# Main_Board_-v1_1.net
KiCad netlist of a schematic drawn in EAGLE
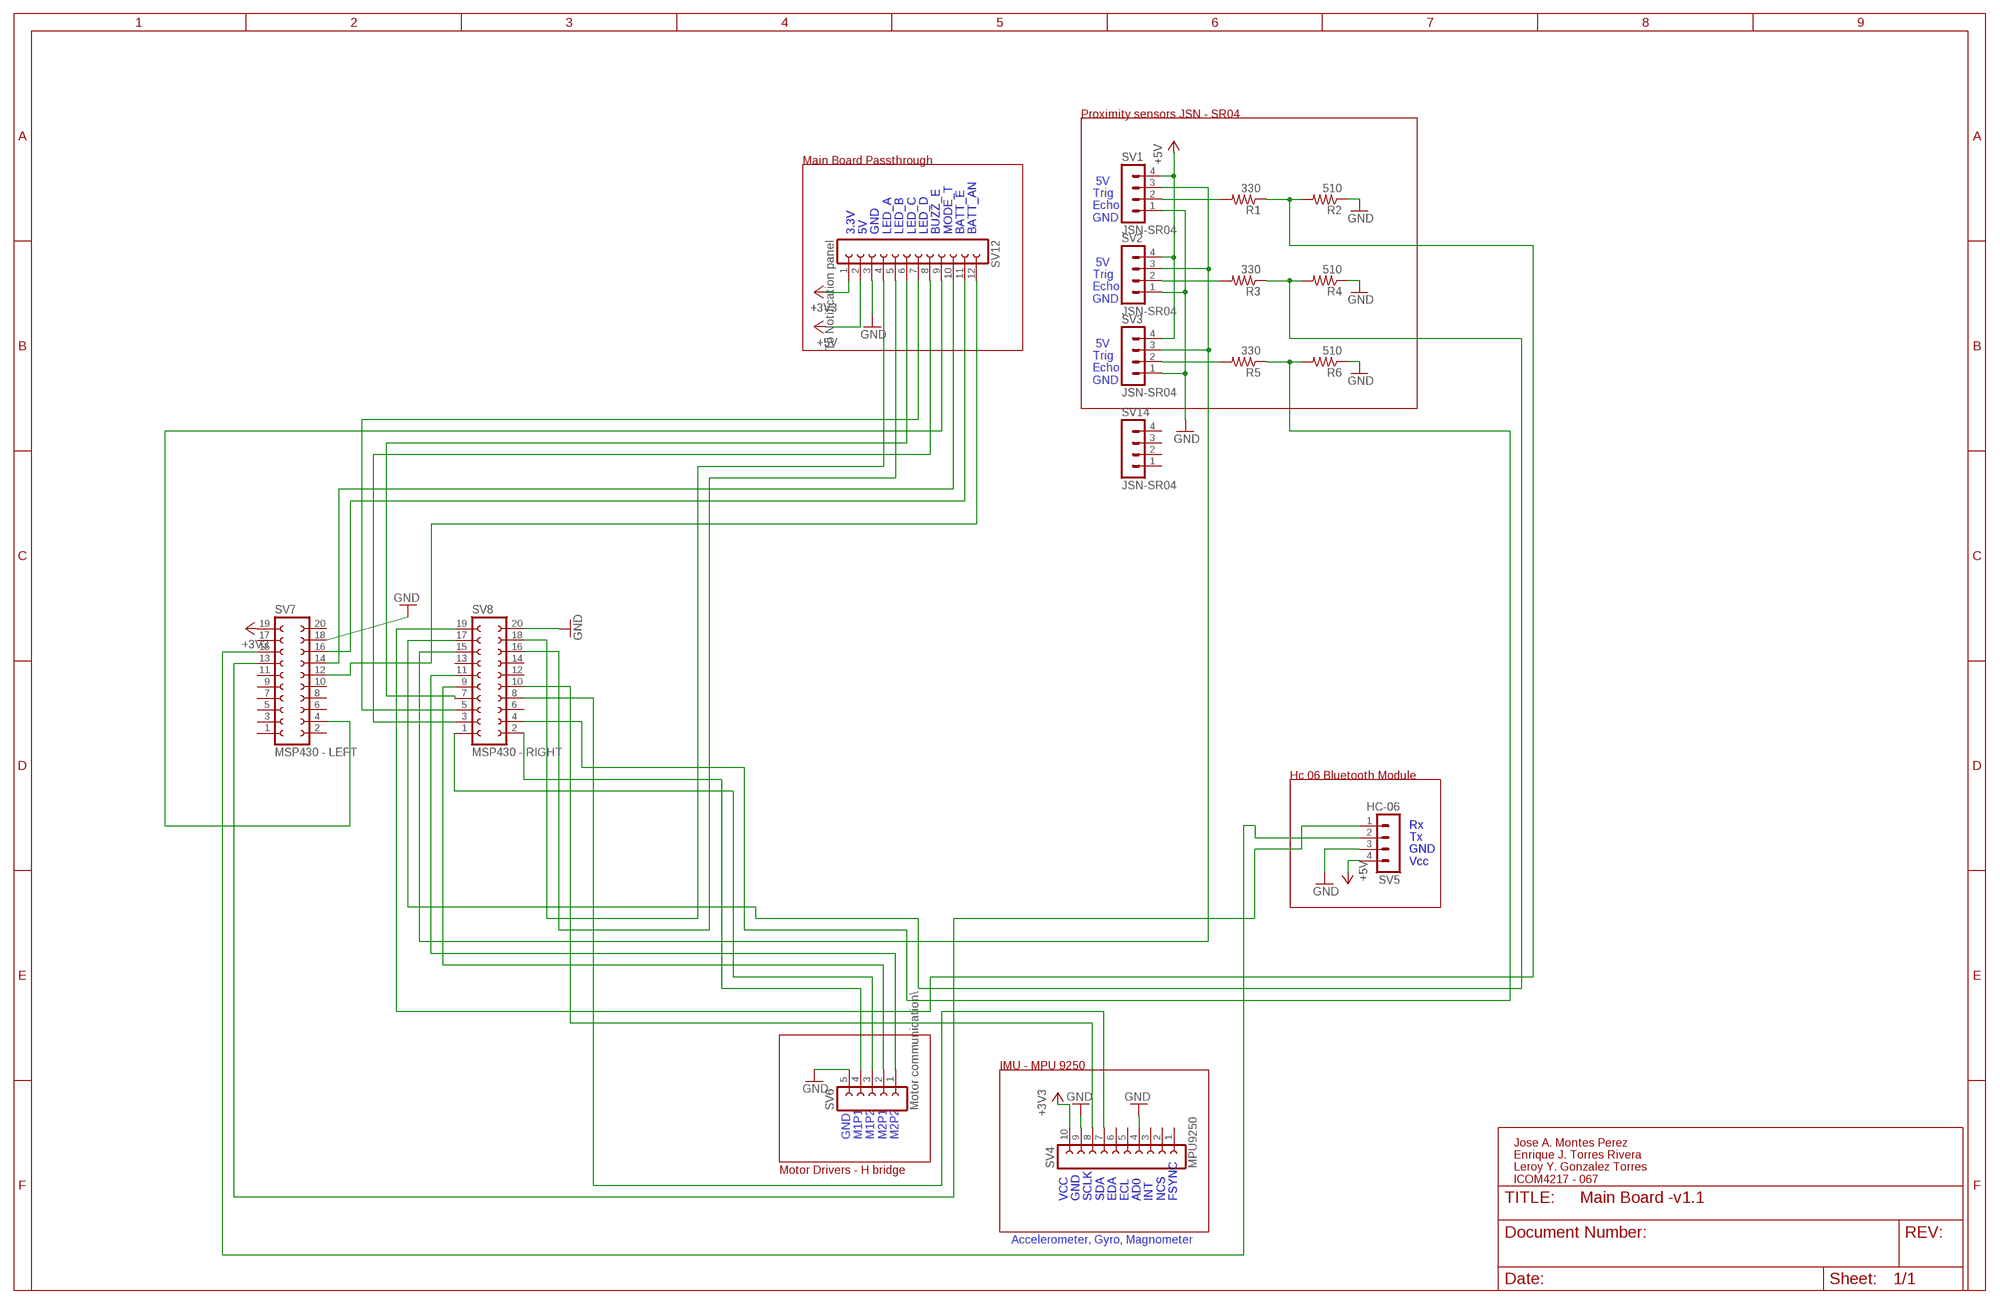
[diagram p0: schematic, sheet 1]

(export (version "E")
  (design (tool "Eeschema 10.0.6"))
  (components
    (comp (ref "R1")
      (value "330")
      (footprint "eagle-import:0207_10")
      (libsource (lib "eagle-import") (part "R-US_0207/10"))
    )
    (comp (ref "R2")
      (value "510")
      (footprint "eagle-import:0207_10")
      (libsource (lib "eagle-import") (part "R-US_0207/10"))
    )
    (comp (ref "R3")
      (value "330")
      (footprint "eagle-import:0207_10")
      (libsource (lib "eagle-import") (part "R-US_0207/10"))
    )
    (comp (ref "R4")
      (value "510")
      (footprint "eagle-import:0207_10")
      (libsource (lib "eagle-import") (part "R-US_0207/10"))
    )
    (comp (ref "R5")
      (value "330")
      (footprint "eagle-import:0207_10")
      (libsource (lib "eagle-import") (part "R-US_0207/10"))
    )
    (comp (ref "R6")
      (value "510")
      (footprint "eagle-import:0207_10")
      (libsource (lib "eagle-import") (part "R-US_0207/10"))
    )
    (comp (ref "SV1")
      (value "JSN-SR04")
      (footprint "eagle-import:MA04-1")
      (libsource (lib "eagle-import") (part "MA04-1"))
    )
    (comp (ref "SV2")
      (value "JSN-SR04")
      (footprint "eagle-import:MA04-1")
      (libsource (lib "eagle-import") (part "MA04-1"))
    )
    (comp (ref "SV3")
      (value "JSN-SR04")
      (footprint "eagle-import:MA04-1")
      (libsource (lib "eagle-import") (part "MA04-1"))
    )
    (comp (ref "SV4")
      (value "MPU9250")
      (footprint "eagle-import:FE10")
      (libsource (lib "eagle-import") (part "FE10-1"))
    )
    (comp (ref "SV5")
      (value "HC-06")
      (footprint "eagle-import:MA04-1")
      (libsource (lib "eagle-import") (part "MA04-1"))
    )
    (comp (ref "SV6")
      (value "Motor communication\\")
      (footprint "eagle-import:FE05-1")
      (libsource (lib "eagle-import") (part "FE05-1"))
    )
    (comp (ref "SV7")
      (value "MSP430 - LEFT")
      (footprint "eagle-import:FE10-2")
      (libsource (lib "eagle-import") (part "FE10-2"))
    )
    (comp (ref "SV8")
      (value "MSP430 - RIGHT")
      (footprint "eagle-import:FE10-2")
      (libsource (lib "eagle-import") (part "FE10-2"))
    )
    (comp (ref "SV12")
      (value "To Notification panel")
      (footprint "eagle-import:FE12")
      (libsource (lib "eagle-import") (part "FE12-1"))
    )
    (comp (ref "SV14")
      (value "JSN-SR04")
      (footprint "eagle-import:MA04-1")
      (libsource (lib "eagle-import") (part "MA04-1"))
    )
  )
  (nets
    (net (code "1") (name "+3V3") (class "Default")
      (node (ref "SV12") (pin "1") (pinfunction "1_1") (pintype "passive"))
      (node (ref "SV4") (pin "10") (pinfunction "10_10") (pintype "passive"))
      (node (ref "SV7") (pin "19") (pinfunction "19_19") (pintype "passive"))
    )
    (net (code "2") (name "+5V") (class "Default")
      (node (ref "SV1") (pin "4") (pinfunction "4_4") (pintype "passive"))
      (node (ref "SV12") (pin "2") (pinfunction "2_2") (pintype "passive"))
      (node (ref "SV2") (pin "4") (pinfunction "4_4") (pintype "passive"))
      (node (ref "SV3") (pin "4") (pinfunction "4_4") (pintype "passive"))
      (node (ref "SV5") (pin "4") (pinfunction "4_4") (pintype "passive"))
    )
    (net (code "3") (name "GND") (class "Default")
      (node (ref "R2") (pin "1") (pinfunction "1_1") (pintype "passive"))
      (node (ref "R4") (pin "1") (pinfunction "1_1") (pintype "passive"))
      (node (ref "R6") (pin "1") (pinfunction "1_1") (pintype "passive"))
      (node (ref "SV1") (pin "1") (pinfunction "1_1") (pintype "passive"))
      (node (ref "SV12") (pin "3") (pinfunction "3_3") (pintype "passive"))
      (node (ref "SV2") (pin "1") (pinfunction "1_1") (pintype "passive"))
      (node (ref "SV3") (pin "1") (pinfunction "1_1") (pintype "passive"))
      (node (ref "SV4") (pin "4") (pinfunction "4_4") (pintype "passive"))
      (node (ref "SV4") (pin "9") (pinfunction "9_9") (pintype "passive"))
      (node (ref "SV5") (pin "3") (pinfunction "3_3") (pintype "passive"))
      (node (ref "SV6") (pin "5") (pinfunction "5_5") (pintype "passive"))
      (node (ref "SV7") (pin "18") (pinfunction "18_18") (pintype "passive"))
      (node (ref "SV8") (pin "20") (pinfunction "20_20") (pintype "passive"))
    )
    (net (code "4") (name "Net-(R1-Pad1)") (class "Default")
      (node (ref "R1") (pin "1") (pinfunction "1_1") (pintype "passive"))
      (node (ref "R2") (pin "2") (pinfunction "2_2") (pintype "passive"))
      (node (ref "SV8") (pin "19") (pinfunction "19_19") (pintype "passive"))
    )
    (net (code "5") (name "Net-(R1-Pad2)") (class "Default")
      (node (ref "R1") (pin "2") (pinfunction "2_2") (pintype "passive"))
      (node (ref "SV1") (pin "2") (pinfunction "2_2") (pintype "passive"))
    )
    (net (code "6") (name "Net-(R3-Pad1)") (class "Default")
      (node (ref "R3") (pin "1") (pinfunction "1_1") (pintype "passive"))
      (node (ref "R4") (pin "2") (pinfunction "2_2") (pintype "passive"))
      (node (ref "SV8") (pin "17") (pinfunction "17_17") (pintype "passive"))
    )
    (net (code "7") (name "Net-(R3-Pad2)") (class "Default")
      (node (ref "R3") (pin "2") (pinfunction "2_2") (pintype "passive"))
      (node (ref "SV2") (pin "2") (pinfunction "2_2") (pintype "passive"))
    )
    (net (code "8") (name "Net-(R5-Pad1)") (class "Default")
      (node (ref "R5") (pin "1") (pinfunction "1_1") (pintype "passive"))
      (node (ref "R6") (pin "2") (pinfunction "2_2") (pintype "passive"))
      (node (ref "SV8") (pin "4") (pinfunction "4_4") (pintype "passive"))
    )
    (net (code "9") (name "Net-(R5-Pad2)") (class "Default")
      (node (ref "R5") (pin "2") (pinfunction "2_2") (pintype "passive"))
      (node (ref "SV3") (pin "2") (pinfunction "2_2") (pintype "passive"))
    )
    (net (code "10") (name "Net-(SV1-Pad3)") (class "Default")
      (node (ref "SV1") (pin "3") (pinfunction "3_3") (pintype "passive"))
      (node (ref "SV2") (pin "3") (pinfunction "3_3") (pintype "passive"))
      (node (ref "SV3") (pin "3") (pinfunction "3_3") (pintype "passive"))
      (node (ref "SV8") (pin "15") (pinfunction "15_15") (pintype "passive"))
    )
    (net (code "11") (name "Net-(SV4-Pad7)") (class "Default")
      (node (ref "SV4") (pin "7") (pinfunction "7_7") (pintype "passive"))
      (node (ref "SV8") (pin "8") (pinfunction "8_8") (pintype "passive"))
    )
    (net (code "12") (name "Net-(SV4-Pad8)") (class "Default")
      (node (ref "SV4") (pin "8") (pinfunction "8_8") (pintype "passive"))
      (node (ref "SV8") (pin "10") (pinfunction "10_10") (pintype "passive"))
    )
    (net (code "13") (name "Net-(SV5-Pad1)") (class "Default")
      (node (ref "SV5") (pin "1") (pinfunction "1_1") (pintype "passive"))
      (node (ref "SV7") (pin "13") (pinfunction "13_13") (pintype "passive"))
    )
    (net (code "14") (name "Net-(SV5-Pad2)") (class "Default")
      (node (ref "SV5") (pin "2") (pinfunction "2_2") (pintype "passive"))
      (node (ref "SV7") (pin "15") (pinfunction "15_15") (pintype "passive"))
    )
    (net (code "15") (name "Net-(SV6-Pad1)") (class "Default")
      (node (ref "SV6") (pin "1") (pinfunction "1_1") (pintype "passive"))
      (node (ref "SV8") (pin "11") (pinfunction "11_11") (pintype "passive"))
    )
    (net (code "16") (name "Net-(SV6-Pad2)") (class "Default")
      (node (ref "SV6") (pin "2") (pinfunction "2_2") (pintype "passive"))
      (node (ref "SV8") (pin "9") (pinfunction "9_9") (pintype "passive"))
    )
    (net (code "17") (name "Net-(SV6-Pad3)") (class "Default")
      (node (ref "SV6") (pin "3") (pinfunction "3_3") (pintype "passive"))
      (node (ref "SV8") (pin "1") (pinfunction "1_1") (pintype "passive"))
    )
    (net (code "18") (name "Net-(SV6-Pad4)") (class "Default")
      (node (ref "SV6") (pin "4") (pinfunction "4_4") (pintype "passive"))
      (node (ref "SV8") (pin "2") (pinfunction "2_2") (pintype "passive"))
    )
    (net (code "19") (name "Net-(SV12-Pad4)") (class "Default")
      (node (ref "SV12") (pin "4") (pinfunction "4_4") (pintype "passive"))
      (node (ref "SV8") (pin "18") (pinfunction "18_18") (pintype "passive"))
    )
    (net (code "20") (name "Net-(SV12-Pad5)") (class "Default")
      (node (ref "SV12") (pin "5") (pinfunction "5_5") (pintype "passive"))
      (node (ref "SV8") (pin "16") (pinfunction "16_16") (pintype "passive"))
    )
    (net (code "21") (name "Net-(SV12-Pad6)") (class "Default")
      (node (ref "SV12") (pin "6") (pinfunction "6_6") (pintype "passive"))
      (node (ref "SV8") (pin "7") (pinfunction "7_7") (pintype "passive"))
    )
    (net (code "22") (name "Net-(SV12-Pad7)") (class "Default")
      (node (ref "SV12") (pin "7") (pinfunction "7_7") (pintype "passive"))
      (node (ref "SV8") (pin "5") (pinfunction "5_5") (pintype "passive"))
    )
    (net (code "23") (name "Net-(SV12-Pad8)") (class "Default")
      (node (ref "SV12") (pin "8") (pinfunction "8_8") (pintype "passive"))
      (node (ref "SV8") (pin "3") (pinfunction "3_3") (pintype "passive"))
    )
    (net (code "24") (name "Net-(SV12-Pad9)") (class "Default")
      (node (ref "SV12") (pin "9") (pinfunction "9_9") (pintype "passive"))
      (node (ref "SV7") (pin "4") (pinfunction "4_4") (pintype "passive"))
    )
    (net (code "25") (name "Net-(SV12-Pad10)") (class "Default")
      (node (ref "SV12") (pin "10") (pinfunction "10_10") (pintype "passive"))
      (node (ref "SV7") (pin "14") (pinfunction "14_14") (pintype "passive"))
    )
    (net (code "26") (name "Net-(SV12-Pad11)") (class "Default")
      (node (ref "SV12") (pin "11") (pinfunction "11_11") (pintype "passive"))
      (node (ref "SV7") (pin "16") (pinfunction "16_16") (pintype "passive"))
    )
    (net (code "27") (name "Net-(SV12-Pad12)") (class "Default")
      (node (ref "SV12") (pin "12") (pinfunction "12_12") (pintype "passive"))
      (node (ref "SV7") (pin "12") (pinfunction "12_12") (pintype "passive"))
    )
    (net (code "28") (name "unconnected-(SV4-Pad1)") (class "Default")
      (node (ref "SV4") (pin "1") (pinfunction "1_1") (pintype "passive"))
    )
    (net (code "29") (name "unconnected-(SV4-Pad2)") (class "Default")
      (node (ref "SV4") (pin "2") (pinfunction "2_2") (pintype "passive"))
    )
    (net (code "30") (name "unconnected-(SV4-Pad3)") (class "Default")
      (node (ref "SV4") (pin "3") (pinfunction "3_3") (pintype "passive"))
    )
    (net (code "31") (name "unconnected-(SV4-Pad5)") (class "Default")
      (node (ref "SV4") (pin "5") (pinfunction "5_5") (pintype "passive"))
    )
    (net (code "32") (name "unconnected-(SV4-Pad6)") (class "Default")
      (node (ref "SV4") (pin "6") (pinfunction "6_6") (pintype "passive"))
    )
    (net (code "33") (name "unconnected-(SV7-Pad1)") (class "Default")
      (node (ref "SV7") (pin "1") (pinfunction "1_1") (pintype "passive"))
    )
    (net (code "34") (name "unconnected-(SV7-Pad2)") (class "Default")
      (node (ref "SV7") (pin "2") (pinfunction "2_2") (pintype "passive"))
    )
    (net (code "35") (name "unconnected-(SV7-Pad3)") (class "Default")
      (node (ref "SV7") (pin "3") (pinfunction "3_3") (pintype "passive"))
    )
    (net (code "36") (name "unconnected-(SV7-Pad5)") (class "Default")
      (node (ref "SV7") (pin "5") (pinfunction "5_5") (pintype "passive"))
    )
    (net (code "37") (name "unconnected-(SV7-Pad6)") (class "Default")
      (node (ref "SV7") (pin "6") (pinfunction "6_6") (pintype "passive"))
    )
    (net (code "38") (name "unconnected-(SV7-Pad7)") (class "Default")
      (node (ref "SV7") (pin "7") (pinfunction "7_7") (pintype "passive"))
    )
    (net (code "39") (name "unconnected-(SV7-Pad8)") (class "Default")
      (node (ref "SV7") (pin "8") (pinfunction "8_8") (pintype "passive"))
    )
    (net (code "40") (name "unconnected-(SV7-Pad9)") (class "Default")
      (node (ref "SV7") (pin "9") (pinfunction "9_9") (pintype "passive"))
    )
    (net (code "41") (name "unconnected-(SV7-Pad10)") (class "Default")
      (node (ref "SV7") (pin "10") (pinfunction "10_10") (pintype "passive"))
    )
    (net (code "42") (name "unconnected-(SV7-Pad11)") (class "Default")
      (node (ref "SV7") (pin "11") (pinfunction "11_11") (pintype "passive"))
    )
    (net (code "43") (name "unconnected-(SV7-Pad17)") (class "Default")
      (node (ref "SV7") (pin "17") (pinfunction "17_17") (pintype "passive"))
    )
    (net (code "44") (name "unconnected-(SV7-Pad20)") (class "Default")
      (node (ref "SV7") (pin "20") (pinfunction "20_20") (pintype "passive"))
    )
    (net (code "45") (name "unconnected-(SV8-Pad6)") (class "Default")
      (node (ref "SV8") (pin "6") (pinfunction "6_6") (pintype "passive"))
    )
    (net (code "46") (name "unconnected-(SV8-Pad12)") (class "Default")
      (node (ref "SV8") (pin "12") (pinfunction "12_12") (pintype "passive"))
    )
    (net (code "47") (name "unconnected-(SV8-Pad13)") (class "Default")
      (node (ref "SV8") (pin "13") (pinfunction "13_13") (pintype "passive"))
    )
    (net (code "48") (name "unconnected-(SV8-Pad14)") (class "Default")
      (node (ref "SV8") (pin "14") (pinfunction "14_14") (pintype "passive"))
    )
    (net (code "49") (name "unconnected-(SV14-Pad1)") (class "Default")
      (node (ref "SV14") (pin "1") (pinfunction "1_1") (pintype "passive"))
    )
    (net (code "50") (name "unconnected-(SV14-Pad2)") (class "Default")
      (node (ref "SV14") (pin "2") (pinfunction "2_2") (pintype "passive"))
    )
    (net (code "51") (name "unconnected-(SV14-Pad3)") (class "Default")
      (node (ref "SV14") (pin "3") (pinfunction "3_3") (pintype "passive"))
    )
    (net (code "52") (name "unconnected-(SV14-Pad4)") (class "Default")
      (node (ref "SV14") (pin "4") (pinfunction "4_4") (pintype "passive"))
    )
  )
)
